# 8V_Buck_LDO_Power.net
KiCad netlist of a schematic drawn in Altium Designer
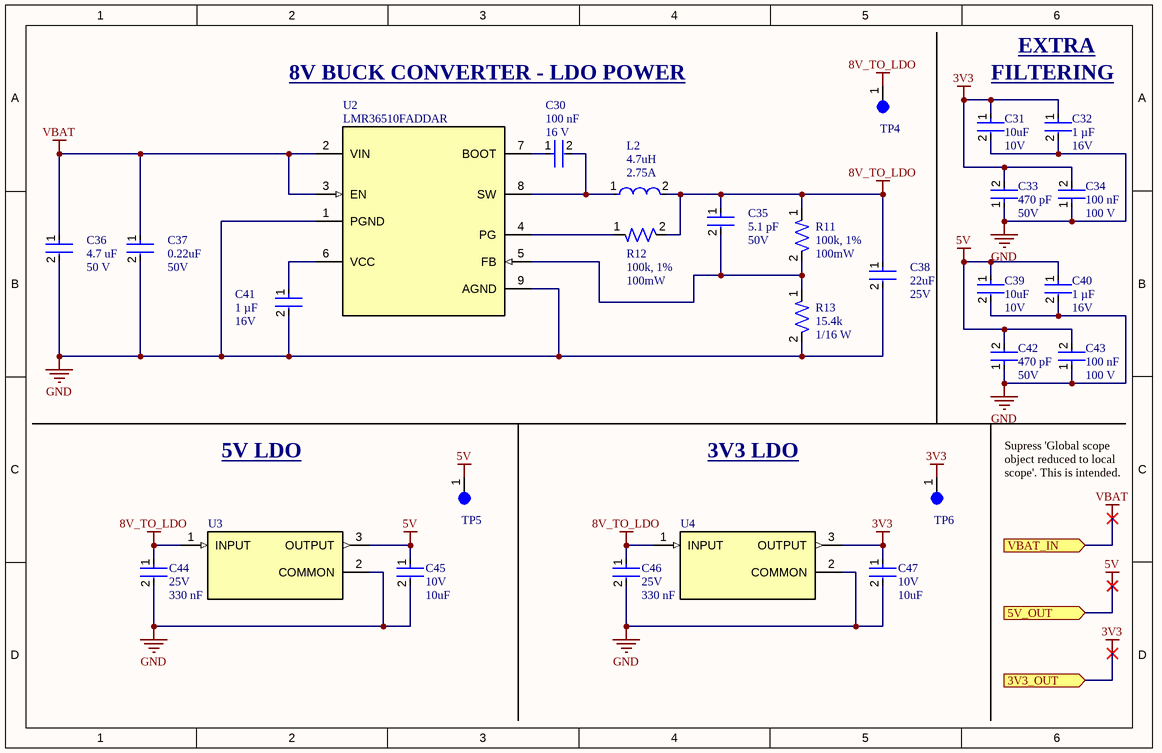
[diagram p0: 8V_Buck_LDO_Power.SchDoc]

(export (version "E")
  (design (tool "Eeschema 10.0.6"))
  (components
    (comp (ref "C30")
      (value "CC0402KRX7R7BB104")
      (footprint "FP-CC0402-IPC_B")
      (description "CAP CER 0.1UF 16V X7R 0402")
      (fields
        (field (name "MANUFACTURER") "YAGEO")
        (field (name "TOLERANCE") "0.1")
        (field (name "VOLTAGE RATING") "16 V")
        (field (name "CAPACITANCE") "100 nF")
      )
      (libsource (lib "JLC_25") (part "CAP-0.1U-0001"))
    )
    (comp (ref "C31")
      (value "CC0603KRX5R6BB106")
      (footprint "FP-CC0603-DC-MFG")
      (description "CAP CER 10UF 10V X5R 0603")
      (fields
        (field (name "TOLERANCE") "10%")
        (field (name "RATED VOLTAGE") "10V")
        (field (name "CAPACITANCE") "10uF")
      )
      (libsource (lib "JLC_25") (part "CAP-10U-0001"))
    )
    (comp (ref "C32")
      (value "CC0603KRX7R7BB105")
      (footprint "FP-CC0603-DA-MFG")
      (description "1 µF ±10% 16V Ceramic Capacitor X7R 0603 (1608 Metric)")
      (fields (field (name "CAPACITANCE") "1 µF") (field (name "VOLTAGE") "16V"))
      (libsource (lib "JLC_25") (part "CAP-1U-0002"))
    )
    (comp (ref "C33")
      (value "CC0805JRNPO9BN471")
      (footprint "CAP_CC0805_YAG-L")
      (description "CAP CER 470PF 50V C0G/NPO 0805")
      (fields (field (name "VOLTAGE") "50V") (field (name "CAPACITANCE") "470 pF"))
      (libsource (lib "JLC_25") (part "CAP-470P-0001"))
    )
    (comp (ref "C34")
      (value "CC0603KRX7R0BB104")
      (footprint "CAP-0603")
      (description "0.1 µF ±10% 100V Ceramic Capacitor X7R 0603 (1608 Metric)")
      (fields (field (name "CAPACITANCE") "100 nF") (field (name "VOLTAGE") "100 V"))
      (libsource (lib "JLC_25") (part "CAP-100N-0001"))
    )
    (comp (ref "C35")
      (value "CC0402CRNPO9BN5R1")
      (footprint "CAPC1005X55N")
      (description "5.1pF Â±0.25pF 50V Ceramic Capacitor C0G, NP0 0402 (1005 Metric)")
      (fields
        (field (name "MF") "Yageo")
        (field (name "VOLTAGE RATING") "50V")
        (field (name "CAPACITANCE") "5.1 pF")
      )
      (libsource (lib "JLC_25") (part "CAP-5.1P-0001"))
    )
    (comp (ref "C36")
      (value "CC0805KKX5R9BB475")
      (footprint "FP-CC0805-0_85-MFG")
      (description "CAP CER 4.7UF 50V X5R 0805")
      (fields
        (field (name "MANUFACTURER") "Yageo")
        (field (name "OCTOPART") "https://octopart.com/cc0805kkx5r9bb475-yageo-81932641")
        (field (name "VOLTAGE RATING") "50 V")
        (field (name "CAPACITANCE") "4.7 uF")
      )
      (libsource (lib "JLC_25") (part "CAP-4.7U-0002"))
    )
    (comp (ref "C37")
      (value "CC0603JRX7R9BB224")
      (footprint "CAP_CC0603_YAG")
      (description "0.22 µF ±5% 50V Ceramic Capacitor X7R 0603 (1608 Metric)")
      (fields (field (name "CAPACITANCE") "0.22uF") (field (name "VOLTAGE") "50V"))
      (libsource (lib "JLC_25") (part "CAP-0.22U-0001"))
    )
    (comp (ref "C38")
      (value "GRM32ER61E226KE15L")
      (footprint "FP-GRM32-MFG")
      (description "CAP CER 22UF 25V X5R 1210")
      (fields
        (field (name "TOLERANCE") "10%")
        (field (name "MANUFACTURER") "Murata Electronics North America")
        (field (name "VOLTAGE - RATED") "25V")
        (field (name "CAPACITANCE") "22uF")
      )
      (libsource (lib "JLC_25") (part "CAP-22U-0001"))
    )
    (comp (ref "C39")
      (value "CC0603KRX5R6BB106")
      (footprint "FP-CC0603-DC-MFG")
      (description "CAP CER 10UF 10V X5R 0603")
      (fields
        (field (name "TOLERANCE") "10%")
        (field (name "RATED VOLTAGE") "10V")
        (field (name "CAPACITANCE") "10uF")
      )
      (libsource (lib "JLC_25") (part "CAP-10U-0001"))
    )
    (comp (ref "C40")
      (value "CC0603KRX7R7BB105")
      (footprint "FP-CC0603-DA-MFG")
      (description "1 µF ±10% 16V Ceramic Capacitor X7R 0603 (1608 Metric)")
      (fields (field (name "CAPACITANCE") "1 µF") (field (name "VOLTAGE") "16V"))
      (libsource (lib "JLC_25") (part "CAP-1U-0002"))
    )
    (comp (ref "C41")
      (value "CC0603KRX7R7BB105")
      (footprint "FP-CC0603-DA-MFG")
      (description "1 µF ±10% 16V Ceramic Capacitor X7R 0603 (1608 Metric)")
      (fields (field (name "CAPACITANCE") "1 µF") (field (name "VOLTAGE") "16V"))
      (libsource (lib "JLC_25") (part "CAP-1U-0002"))
    )
    (comp (ref "C42")
      (value "CC0805JRNPO9BN471")
      (footprint "CAP_CC0805_YAG-L")
      (description "CAP CER 470PF 50V C0G/NPO 0805")
      (fields (field (name "VOLTAGE") "50V") (field (name "CAPACITANCE") "470 pF"))
      (libsource (lib "JLC_25") (part "CAP-470P-0001"))
    )
    (comp (ref "C43")
      (value "CC0603KRX7R0BB104")
      (footprint "CAP-0603")
      (description "0.1 µF ±10% 100V Ceramic Capacitor X7R 0603 (1608 Metric)")
      (fields (field (name "CAPACITANCE") "100 nF") (field (name "VOLTAGE") "100 V"))
      (libsource (lib "JLC_25") (part "CAP-100N-0001"))
    )
    (comp (ref "C44")
      (value "CC0603KRX7R8BB334")
      (footprint "FP-CC0603-DA-MFG")
      (description "CAP CER 0.33UF 25V X7R 0603")
      (fields
        (field (name "VOLTAGE") "25 V")
        (field (name "OCTOPART") "https://octopart.com/cc0603krx7r8bb334-yageo-47255252")
        (field (name "RATED VOLTAGE") "25V")
        (field (name "CAPACITANCE") "330 nF")
      )
      (libsource (lib "JLC_25") (part "CAP-0.33U-0001"))
    )
    (comp (ref "C45")
      (value "CC0603KRX5R6BB106")
      (footprint "FP-CC0603-DC-MFG")
      (description "CAP CER 10UF 10V X5R 0603")
      (fields
        (field (name "TOLERANCE") "10%")
        (field (name "RATED VOLTAGE") "10V")
        (field (name "CAPACITANCE") "10uF")
      )
      (libsource (lib "JLC_25") (part "CAP-10U-0001"))
    )
    (comp (ref "C46")
      (value "CC0603KRX7R8BB334")
      (footprint "FP-CC0603-DA-MFG")
      (description "CAP CER 0.33UF 25V X7R 0603")
      (fields
        (field (name "VOLTAGE") "25 V")
        (field (name "OCTOPART") "https://octopart.com/cc0603krx7r8bb334-yageo-47255252")
        (field (name "RATED VOLTAGE") "25V")
        (field (name "CAPACITANCE") "330 nF")
      )
      (libsource (lib "JLC_25") (part "CAP-0.33U-0001"))
    )
    (comp (ref "C47")
      (value "CC0603KRX5R6BB106")
      (footprint "FP-CC0603-DC-MFG")
      (description "CAP CER 10UF 10V X5R 0603")
      (fields
        (field (name "TOLERANCE") "10%")
        (field (name "RATED VOLTAGE") "10V")
        (field (name "CAPACITANCE") "10uF")
      )
      (libsource (lib "JLC_25") (part "CAP-10U-0001"))
    )
    (comp (ref "L2")
      (value "CDRH104NP-221MC")
      (footprint "IND-4.7UH-0001")
      (description "FIXED IND 220UH 520MA 960MOHM SM")
      (fields (field (name "INDUCTANCE") "4.7uH") (field (name "CURRENT RATING") "2.75A"))
      (libsource (lib "JLC_25") (part "IND-4.7U-0001"))
    )
    (comp (ref "R11")
      (value "RC0603FR-07100KL")
      (footprint "FP-RC0603-0_55-IPC_B")
      (description "RES SMD 100K OHM 1% 1/10W 0603")
      (fields
        (field (name "TOLERANCE") "1%")
        (field (name "POWER") "100mW")
        (field (name "RESISTANCE") "100k, 1%")
      )
      (libsource (lib "JLC_25") (part "RES-100k-0001"))
    )
    (comp (ref "R12")
      (value "RC0603FR-07100KL")
      (footprint "FP-RC0603-0_55-IPC_B")
      (description "RES SMD 100K OHM 1% 1/10W 0603")
      (fields
        (field (name "TOLERANCE") "1%")
        (field (name "POWER") "100mW")
        (field (name "RESISTANCE") "100k, 1%")
      )
      (libsource (lib "JLC_25") (part "RES-100k-0001"))
    )
    (comp (ref "R13")
      (value "AC0402FR-0715K4L")
      (footprint "FP-AC0402-MFG")
      (description "RES 15.4kΩ ±1% 0.063W 0402")
      (fields
        (field (name "TOLERANCE") "1%")
        (field (name "POWER RATING") "1/16 W")
        (field (name "RESISTANCE") "15.4k")
      )
      (libsource (lib "JLC_25") (part "RES-15.4K-0001"))
    )
    (comp (ref "TP4")
      (value "5003")
      (footprint "TEST-POINT-0001")
      (description "Oranange PC Test Point, Miniature Phoisphor Bronze Silver Plating Through Hole Mounting Type")
      (libsource (lib "*") (part "TEST-POINT-0001"))
    )
    (comp (ref "TP5")
      (value "5003")
      (footprint "TEST-POINT-0001")
      (description "Oranange PC Test Point, Miniature Phoisphor Bronze Silver Plating Through Hole Mounting Type")
      (libsource (lib "*") (part "TEST-POINT-0001"))
    )
    (comp (ref "TP6")
      (value "5003")
      (footprint "TEST-POINT-0001")
      (description "Oranange PC Test Point, Miniature Phoisphor Bronze Silver Plating Through Hole Mounting Type")
      (libsource (lib "*") (part "TEST-POINT-0001"))
    )
    (comp (ref "U2")
      (value "LMR36510FADDAR")
      (footprint "DDA0008J")
      (description "Buck Switching Regulator IC Positive Adjustable 1V 1 Output 1A 8-PowerSOIC (0.154\", 3.90mm Width)")
      (libsource (lib "JLC_25") (part "IC-BUCK-0003"))
    )
    (comp (ref "U3")
      (value "UA78M05IDCYR")
      (footprint "FP-DCY0004A-IPC_B")
      (description "IC REG LINEAR 5V 500MA SOT223-4")
      (fields
        (field (name "OCTOPART") "https://octopart.com/ua78m05idcyr-texas+instruments-525575")
        (field (name "MANUFACTURER") "Texas Instruments")
      )
      (libsource (lib "JLC_25") (part "IC-LDO-0001"))
    )
    (comp (ref "U4")
      (value "UA78M33CDCYR")
      (footprint "VREG_UA78M33CDCYR")
      (description "IC REG LIN 3.3V 500MA SOT223-4")
      (fields (field (name "MF") "Texas Instruments"))
      (libsource (lib "JLC_25") (part "IC-LDO-0002"))
    )
  )
  (nets
    (net (code "1") (name "3V3") (class "Default")
      (node (ref "C31") (pin "1") (pinfunction "1_1") (pintype "passive"))
      (node (ref "C32") (pin "1") (pinfunction "1_1") (pintype "passive"))
      (node (ref "C33") (pin "2") (pinfunction "2_2") (pintype "passive"))
      (node (ref "C34") (pin "2") (pinfunction "2_2") (pintype "passive"))
      (node (ref "C47") (pin "1") (pinfunction "1_1") (pintype "passive"))
      (node (ref "TP6") (pin "1") (pinfunction "0_1") (pintype "passive"))
      (node (ref "U4") (pin "3") (pinfunction "OUTPUT_3") (pintype "output"))
    )
    (net (code "2") (name "5V") (class "Default")
      (node (ref "C39") (pin "1") (pinfunction "1_1") (pintype "passive"))
      (node (ref "C40") (pin "1") (pinfunction "1_1") (pintype "passive"))
      (node (ref "C42") (pin "2") (pinfunction "2_2") (pintype "passive"))
      (node (ref "C43") (pin "2") (pinfunction "2_2") (pintype "passive"))
      (node (ref "C45") (pin "1") (pinfunction "1_1") (pintype "passive"))
      (node (ref "TP5") (pin "1") (pinfunction "0_1") (pintype "passive"))
      (node (ref "U3") (pin "3") (pinfunction "OUTPUT_3") (pintype "output"))
    )
    (net (code "3") (name "8V_TO_LDO") (class "Default")
      (node (ref "C35") (pin "1") (pinfunction "1_1") (pintype "passive"))
      (node (ref "C38") (pin "1") (pinfunction "1_1") (pintype "passive"))
      (node (ref "C44") (pin "1") (pinfunction "1_1") (pintype "passive"))
      (node (ref "C46") (pin "1") (pinfunction "1_1") (pintype "passive"))
      (node (ref "L2") (pin "2") (pinfunction "2_2") (pintype "passive"))
      (node (ref "R11") (pin "1") (pinfunction "1_1") (pintype "passive"))
      (node (ref "R12") (pin "2") (pinfunction "2_2") (pintype "passive"))
      (node (ref "TP4") (pin "1") (pinfunction "0_1") (pintype "passive"))
      (node (ref "U3") (pin "1") (pinfunction "INPUT_1") (pintype "input"))
      (node (ref "U4") (pin "1") (pinfunction "INPUT_1") (pintype "input"))
    )
    (net (code "4") (name "GND") (class "Default")
      (node (ref "C31") (pin "2") (pinfunction "2_2") (pintype "passive"))
      (node (ref "C32") (pin "2") (pinfunction "2_2") (pintype "passive"))
      (node (ref "C33") (pin "1") (pinfunction "1_1") (pintype "passive"))
      (node (ref "C34") (pin "1") (pinfunction "1_1") (pintype "passive"))
      (node (ref "C36") (pin "2") (pinfunction "2_2") (pintype "passive"))
      (node (ref "C37") (pin "2") (pinfunction "2_2") (pintype "passive"))
      (node (ref "C38") (pin "2") (pinfunction "2_2") (pintype "passive"))
      (node (ref "C39") (pin "2") (pinfunction "2_2") (pintype "passive"))
      (node (ref "C40") (pin "2") (pinfunction "2_2") (pintype "passive"))
      (node (ref "C41") (pin "2") (pinfunction "2_2") (pintype "passive"))
      (node (ref "C42") (pin "1") (pinfunction "1_1") (pintype "passive"))
      (node (ref "C43") (pin "1") (pinfunction "1_1") (pintype "passive"))
      (node (ref "C44") (pin "2") (pinfunction "2_2") (pintype "passive"))
      (node (ref "C45") (pin "2") (pinfunction "2_2") (pintype "passive"))
      (node (ref "C46") (pin "2") (pinfunction "2_2") (pintype "passive"))
      (node (ref "C47") (pin "2") (pinfunction "2_2") (pintype "passive"))
      (node (ref "R13") (pin "2") (pinfunction "2_2") (pintype "passive"))
      (node (ref "U2") (pin "1") (pinfunction "PGND_1") (pintype "power_in"))
      (node (ref "U2") (pin "9") (pinfunction "AGND_9") (pintype "passive"))
      (node (ref "U3") (pin "2") (pinfunction "COMMON_2") (pintype "passive"))
      (node (ref "U4") (pin "2") (pinfunction "COMMON_2") (pintype "power_in"))
    )
    (net (code "5") (name "Net-(U2-BOOT)") (class "Default")
      (node (ref "C30") (pin "1") (pinfunction "1_1") (pintype "passive"))
      (node (ref "U2") (pin "7") (pinfunction "BOOT_7") (pintype "power_in"))
    )
    (net (code "6") (name "Net-(U2-FB)") (class "Default")
      (node (ref "C35") (pin "2") (pinfunction "2_2") (pintype "passive"))
      (node (ref "R11") (pin "2") (pinfunction "2_2") (pintype "passive"))
      (node (ref "R13") (pin "1") (pinfunction "1_1") (pintype "passive"))
      (node (ref "U2") (pin "5") (pinfunction "FB_5") (pintype "input"))
    )
    (net (code "7") (name "Net-(U2-PG)") (class "Default")
      (node (ref "R12") (pin "1") (pinfunction "1_1") (pintype "passive"))
      (node (ref "U2") (pin "4") (pinfunction "PG_4") (pintype "open_collector"))
    )
    (net (code "8") (name "Net-(U2-SW)") (class "Default")
      (node (ref "C30") (pin "2") (pinfunction "2_2") (pintype "passive"))
      (node (ref "L2") (pin "1") (pinfunction "1_1") (pintype "passive"))
      (node (ref "U2") (pin "8") (pinfunction "SW_8") (pintype "power_in"))
    )
    (net (code "9") (name "Net-(U2-VCC)") (class "Default")
      (node (ref "C41") (pin "1") (pinfunction "1_1") (pintype "passive"))
      (node (ref "U2") (pin "6") (pinfunction "VCC_6") (pintype "power_in"))
    )
    (net (code "10") (name "VBAT") (class "Default")
      (node (ref "C36") (pin "1") (pinfunction "1_1") (pintype "passive"))
      (node (ref "C37") (pin "1") (pinfunction "1_1") (pintype "passive"))
      (node (ref "U2") (pin "2") (pinfunction "VIN_2") (pintype "power_in"))
      (node (ref "U2") (pin "3") (pinfunction "EN_3") (pintype "input"))
    )
  )
)
